# HuBreakout_rev_A_layer1.net
KiCad netlist of a schematic drawn in EAGLE
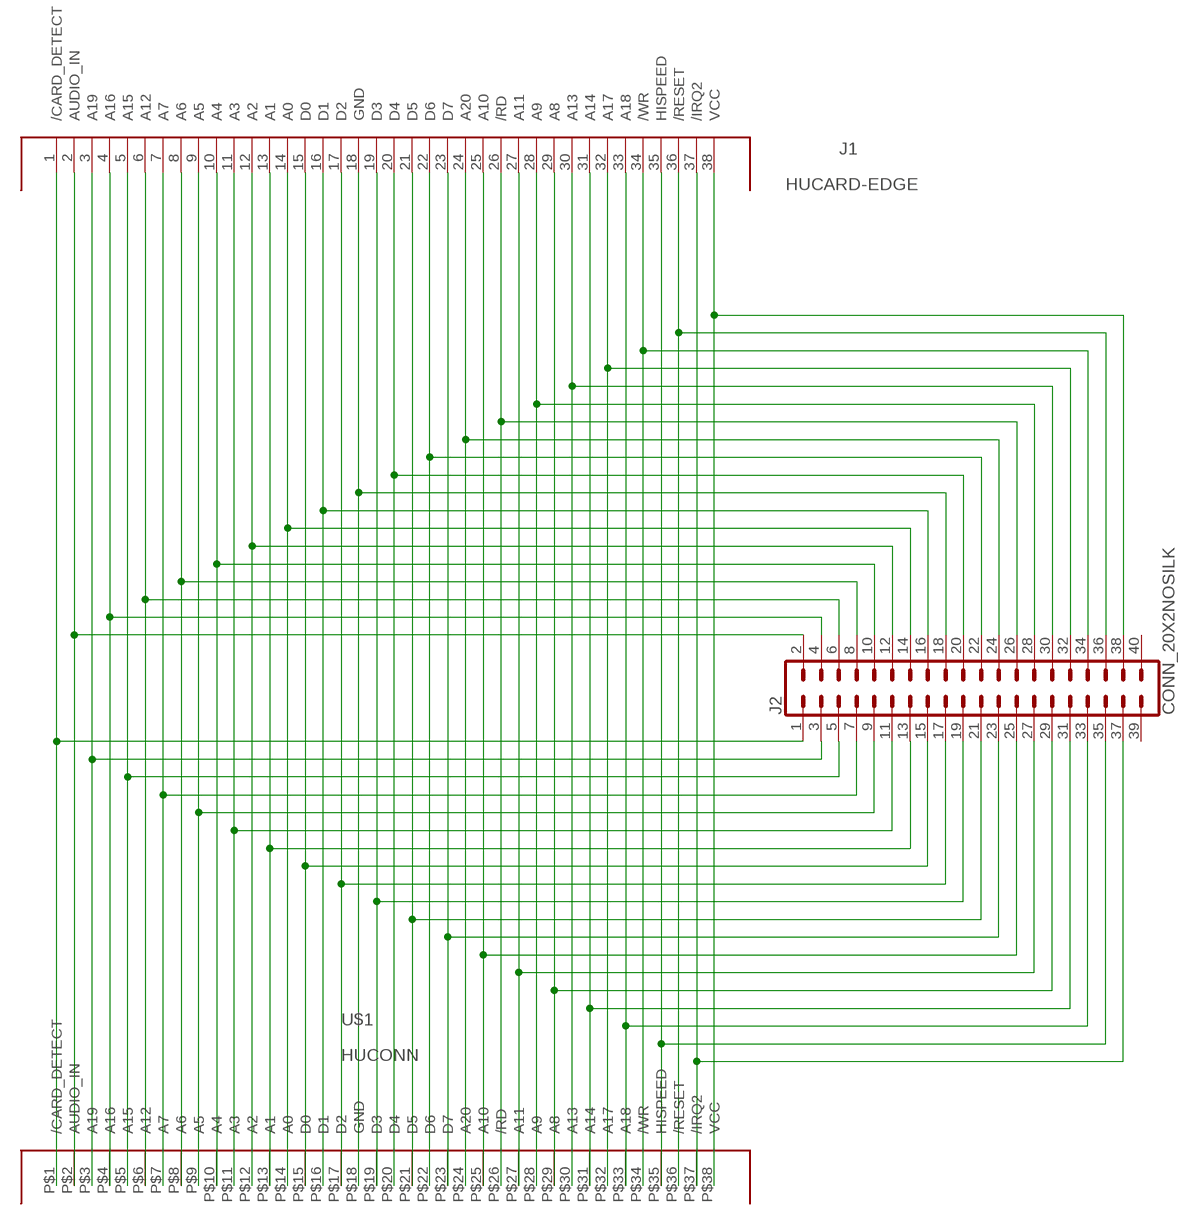
[diagram p0: schematic, sheet 1]

(export (version "E")
  (design (tool "Eeschema 10.0.6"))
  (components
    (comp (ref "J1")
      (value "HUCARD-EDGE")
      (footprint "eagle-import:HUCARD-EDGE")
      (libsource (lib "eagle-import") (part "HUCARD-EDGE"))
    )
    (comp (ref "J2")
      (value "CONN_20X2NOSILK")
      (footprint "eagle-import:2X20_NOSILK")
      (libsource (lib "eagle-import") (part "CONN_20X2NOSILK"))
    )
    (comp (ref "U$1")
      (value "HUCONN")
      (footprint "eagle-import:HUCONN")
      (libsource (lib "eagle-import") (part "HUCONN"))
    )
  )
  (nets
    (net (code "1") (name "Net-(J1-A0)") (class "Default")
      (node (ref "J1") (pin "14") (pinfunction "A0_14") (pintype "output"))
      (node (ref "J2") (pin "14") (pinfunction "14_14") (pintype "passive"))
      (node (ref "U$1") (pin "P$14") (pinfunction "A0_P$14") (pintype "output"))
    )
    (net (code "2") (name "Net-(J1-A1)") (class "Default")
      (node (ref "J1") (pin "13") (pinfunction "A1_13") (pintype "output"))
      (node (ref "J2") (pin "13") (pinfunction "13_13") (pintype "passive"))
      (node (ref "U$1") (pin "P$13") (pinfunction "A1_P$13") (pintype "output"))
    )
    (net (code "3") (name "Net-(J1-A2)") (class "Default")
      (node (ref "J1") (pin "12") (pinfunction "A2_12") (pintype "output"))
      (node (ref "J2") (pin "12") (pinfunction "12_12") (pintype "passive"))
      (node (ref "U$1") (pin "P$12") (pinfunction "A2_P$12") (pintype "output"))
    )
    (net (code "4") (name "Net-(J1-A3)") (class "Default")
      (node (ref "J1") (pin "11") (pinfunction "A3_11") (pintype "output"))
      (node (ref "J2") (pin "11") (pinfunction "11_11") (pintype "passive"))
      (node (ref "U$1") (pin "P$11") (pinfunction "A3_P$11") (pintype "output"))
    )
    (net (code "5") (name "Net-(J1-A4)") (class "Default")
      (node (ref "J1") (pin "10") (pinfunction "A4_10") (pintype "output"))
      (node (ref "J2") (pin "10") (pinfunction "10_10") (pintype "passive"))
      (node (ref "U$1") (pin "P$10") (pinfunction "A4_P$10") (pintype "output"))
    )
    (net (code "6") (name "Net-(J1-A5)") (class "Default")
      (node (ref "J1") (pin "9") (pinfunction "A5_9") (pintype "output"))
      (node (ref "J2") (pin "9") (pinfunction "9_9") (pintype "passive"))
      (node (ref "U$1") (pin "P$9") (pinfunction "A5_P$9") (pintype "output"))
    )
    (net (code "7") (name "Net-(J1-A6)") (class "Default")
      (node (ref "J1") (pin "8") (pinfunction "A6_8") (pintype "output"))
      (node (ref "J2") (pin "8") (pinfunction "8_8") (pintype "passive"))
      (node (ref "U$1") (pin "P$8") (pinfunction "A6_P$8") (pintype "output"))
    )
    (net (code "8") (name "Net-(J1-A7)") (class "Default")
      (node (ref "J1") (pin "7") (pinfunction "A7_7") (pintype "output"))
      (node (ref "J2") (pin "7") (pinfunction "7_7") (pintype "passive"))
      (node (ref "U$1") (pin "P$7") (pinfunction "A7_P$7") (pintype "output"))
    )
    (net (code "9") (name "Net-(J1-A8)") (class "Default")
      (node (ref "J1") (pin "29") (pinfunction "A8_29") (pintype "output"))
      (node (ref "J2") (pin "29") (pinfunction "29_29") (pintype "passive"))
      (node (ref "U$1") (pin "P$29") (pinfunction "A8_P$29") (pintype "output"))
    )
    (net (code "10") (name "Net-(J1-A9)") (class "Default")
      (node (ref "J1") (pin "28") (pinfunction "A9_28") (pintype "output"))
      (node (ref "J2") (pin "28") (pinfunction "28_28") (pintype "passive"))
      (node (ref "U$1") (pin "P$28") (pinfunction "A9_P$28") (pintype "output"))
    )
    (net (code "11") (name "Net-(J1-A10)") (class "Default")
      (node (ref "J1") (pin "25") (pinfunction "A10_25") (pintype "output"))
      (node (ref "J2") (pin "25") (pinfunction "25_25") (pintype "passive"))
      (node (ref "U$1") (pin "P$25") (pinfunction "A10_P$25") (pintype "output"))
    )
    (net (code "12") (name "Net-(J1-A11)") (class "Default")
      (node (ref "J1") (pin "27") (pinfunction "A11_27") (pintype "output"))
      (node (ref "J2") (pin "27") (pinfunction "27_27") (pintype "passive"))
      (node (ref "U$1") (pin "P$27") (pinfunction "A11_P$27") (pintype "output"))
    )
    (net (code "13") (name "Net-(J1-A12)") (class "Default")
      (node (ref "J1") (pin "6") (pinfunction "A12_6") (pintype "output"))
      (node (ref "J2") (pin "6") (pinfunction "6_6") (pintype "passive"))
      (node (ref "U$1") (pin "P$6") (pinfunction "A12_P$6") (pintype "output"))
    )
    (net (code "14") (name "Net-(J1-A13)") (class "Default")
      (node (ref "J1") (pin "30") (pinfunction "A13_30") (pintype "output"))
      (node (ref "J2") (pin "30") (pinfunction "30_30") (pintype "passive"))
      (node (ref "U$1") (pin "P$30") (pinfunction "A13_P$30") (pintype "output"))
    )
    (net (code "15") (name "Net-(J1-A14)") (class "Default")
      (node (ref "J1") (pin "31") (pinfunction "A14_31") (pintype "output"))
      (node (ref "J2") (pin "31") (pinfunction "31_31") (pintype "passive"))
      (node (ref "U$1") (pin "P$31") (pinfunction "A14_P$31") (pintype "output"))
    )
    (net (code "16") (name "Net-(J1-A15)") (class "Default")
      (node (ref "J1") (pin "5") (pinfunction "A15_5") (pintype "output"))
      (node (ref "J2") (pin "5") (pinfunction "5_5") (pintype "passive"))
      (node (ref "U$1") (pin "P$5") (pinfunction "A15_P$5") (pintype "output"))
    )
    (net (code "17") (name "Net-(J1-A16)") (class "Default")
      (node (ref "J1") (pin "4") (pinfunction "A16_4") (pintype "output"))
      (node (ref "J2") (pin "4") (pinfunction "4_4") (pintype "passive"))
      (node (ref "U$1") (pin "P$4") (pinfunction "A16_P$4") (pintype "output"))
    )
    (net (code "18") (name "Net-(J1-A17)") (class "Default")
      (node (ref "J1") (pin "32") (pinfunction "A17_32") (pintype "output"))
      (node (ref "J2") (pin "32") (pinfunction "32_32") (pintype "passive"))
      (node (ref "U$1") (pin "P$32") (pinfunction "A17_P$32") (pintype "output"))
    )
    (net (code "19") (name "Net-(J1-A18)") (class "Default")
      (node (ref "J1") (pin "33") (pinfunction "A18_33") (pintype "output"))
      (node (ref "J2") (pin "33") (pinfunction "33_33") (pintype "passive"))
      (node (ref "U$1") (pin "P$33") (pinfunction "A18_P$33") (pintype "output"))
    )
    (net (code "20") (name "Net-(J1-A19)") (class "Default")
      (node (ref "J1") (pin "3") (pinfunction "A19_3") (pintype "output"))
      (node (ref "J2") (pin "3") (pinfunction "3_3") (pintype "passive"))
      (node (ref "U$1") (pin "P$3") (pinfunction "A19_P$3") (pintype "output"))
    )
    (net (code "21") (name "Net-(J1-A20)") (class "Default")
      (node (ref "J1") (pin "24") (pinfunction "A20_24") (pintype "output"))
      (node (ref "J2") (pin "24") (pinfunction "24_24") (pintype "passive"))
      (node (ref "U$1") (pin "P$24") (pinfunction "A20_P$24") (pintype "output"))
    )
    (net (code "22") (name "Net-(J1-AUDIO_IN)") (class "Default")
      (node (ref "J1") (pin "2") (pinfunction "AUDIO_IN_2") (pintype "input"))
      (node (ref "J2") (pin "2") (pinfunction "2_2") (pintype "passive"))
      (node (ref "U$1") (pin "P$2") (pinfunction "AUDIO_IN_P$2") (pintype "input"))
    )
    (net (code "23") (name "Net-(J1-D0)") (class "Default")
      (node (ref "J1") (pin "15") (pinfunction "D0_15") (pintype "bidirectional"))
      (node (ref "J2") (pin "15") (pinfunction "15_15") (pintype "passive"))
      (node (ref "U$1") (pin "P$15") (pinfunction "D0_P$15") (pintype "bidirectional"))
    )
    (net (code "24") (name "Net-(J1-D1)") (class "Default")
      (node (ref "J1") (pin "16") (pinfunction "D1_16") (pintype "bidirectional"))
      (node (ref "J2") (pin "16") (pinfunction "16_16") (pintype "passive"))
      (node (ref "U$1") (pin "P$16") (pinfunction "D1_P$16") (pintype "bidirectional"))
    )
    (net (code "25") (name "Net-(J1-D2)") (class "Default")
      (node (ref "J1") (pin "17") (pinfunction "D2_17") (pintype "bidirectional"))
      (node (ref "J2") (pin "17") (pinfunction "17_17") (pintype "passive"))
      (node (ref "U$1") (pin "P$17") (pinfunction "D2_P$17") (pintype "bidirectional"))
    )
    (net (code "26") (name "Net-(J1-D3)") (class "Default")
      (node (ref "J1") (pin "19") (pinfunction "D3_19") (pintype "bidirectional"))
      (node (ref "J2") (pin "19") (pinfunction "19_19") (pintype "passive"))
      (node (ref "U$1") (pin "P$19") (pinfunction "D3_P$19") (pintype "bidirectional"))
    )
    (net (code "27") (name "Net-(J1-D4)") (class "Default")
      (node (ref "J1") (pin "20") (pinfunction "D4_20") (pintype "bidirectional"))
      (node (ref "J2") (pin "20") (pinfunction "20_20") (pintype "passive"))
      (node (ref "U$1") (pin "P$20") (pinfunction "D4_P$20") (pintype "bidirectional"))
    )
    (net (code "28") (name "Net-(J1-D5)") (class "Default")
      (node (ref "J1") (pin "21") (pinfunction "D5_21") (pintype "bidirectional"))
      (node (ref "J2") (pin "21") (pinfunction "21_21") (pintype "passive"))
      (node (ref "U$1") (pin "P$21") (pinfunction "D5_P$21") (pintype "bidirectional"))
    )
    (net (code "29") (name "Net-(J1-D6)") (class "Default")
      (node (ref "J1") (pin "22") (pinfunction "D6_22") (pintype "bidirectional"))
      (node (ref "J2") (pin "22") (pinfunction "22_22") (pintype "passive"))
      (node (ref "U$1") (pin "P$22") (pinfunction "D6_P$22") (pintype "bidirectional"))
    )
    (net (code "30") (name "Net-(J1-D7)") (class "Default")
      (node (ref "J1") (pin "23") (pinfunction "D7_23") (pintype "bidirectional"))
      (node (ref "J2") (pin "23") (pinfunction "23_23") (pintype "passive"))
      (node (ref "U$1") (pin "P$23") (pinfunction "D7_P$23") (pintype "bidirectional"))
    )
    (net (code "31") (name "Net-(J1-GND)") (class "Default")
      (node (ref "J1") (pin "18") (pinfunction "GND_18") (pintype "power_in"))
      (node (ref "J2") (pin "18") (pinfunction "18_18") (pintype "passive"))
      (node (ref "U$1") (pin "P$18") (pinfunction "GND_P$18") (pintype "power_in"))
    )
    (net (code "32") (name "Net-(J1-HISPEED)") (class "Default")
      (node (ref "J1") (pin "35") (pinfunction "HISPEED_35") (pintype "output"))
      (node (ref "J2") (pin "35") (pinfunction "35_35") (pintype "passive"))
      (node (ref "U$1") (pin "P$35") (pinfunction "HISPEED_P$35") (pintype "output"))
    )
    (net (code "33") (name "Net-(J1-VCC)") (class "Default")
      (node (ref "J1") (pin "38") (pinfunction "VCC_38") (pintype "power_in"))
      (node (ref "J2") (pin "38") (pinfunction "38_38") (pintype "passive"))
      (node (ref "U$1") (pin "P$38") (pinfunction "VCC_P$38") (pintype "power_in"))
    )
    (net (code "34") (name "Net-(J1-{slash}CARD_DETECT)") (class "Default")
      (node (ref "J1") (pin "1") (pinfunction "/CARD_DETECT_1") (pintype "input"))
      (node (ref "J2") (pin "1") (pinfunction "1_1") (pintype "passive"))
      (node (ref "U$1") (pin "P$1") (pinfunction "/CARD_DETECT_P$1") (pintype "input"))
    )
    (net (code "35") (name "Net-(J1-{slash}IRQ2)") (class "Default")
      (node (ref "J1") (pin "37") (pinfunction "/IRQ2_37") (pintype "bidirectional"))
      (node (ref "J2") (pin "37") (pinfunction "37_37") (pintype "passive"))
      (node (ref "U$1") (pin "P$37") (pinfunction "/IRQ2_P$37") (pintype "bidirectional"))
    )
    (net (code "36") (name "Net-(J1-{slash}RD)") (class "Default")
      (node (ref "J1") (pin "26") (pinfunction "/RD_26") (pintype "output"))
      (node (ref "J2") (pin "26") (pinfunction "26_26") (pintype "passive"))
      (node (ref "U$1") (pin "P$26") (pinfunction "/RD_P$26") (pintype "output"))
    )
    (net (code "37") (name "Net-(J1-{slash}RESET)") (class "Default")
      (node (ref "J1") (pin "36") (pinfunction "/RESET_36") (pintype "bidirectional"))
      (node (ref "J2") (pin "36") (pinfunction "36_36") (pintype "passive"))
      (node (ref "U$1") (pin "P$36") (pinfunction "/RESET_P$36") (pintype "bidirectional"))
    )
    (net (code "38") (name "Net-(J1-{slash}WR)") (class "Default")
      (node (ref "J1") (pin "34") (pinfunction "/WR_34") (pintype "output"))
      (node (ref "J2") (pin "34") (pinfunction "34_34") (pintype "passive"))
      (node (ref "U$1") (pin "P$34") (pinfunction "/WR_P$34") (pintype "output"))
    )
    (net (code "39") (name "unconnected-(J2-Pad39)") (class "Default")
      (node (ref "J2") (pin "39") (pinfunction "39_39") (pintype "passive"))
    )
    (net (code "40") (name "unconnected-(J2-Pad40)") (class "Default")
      (node (ref "J2") (pin "40") (pinfunction "40_40") (pintype "passive"))
    )
  )
)
